# motor_driver.net
KiCad netlist of a schematic drawn in EAGLE
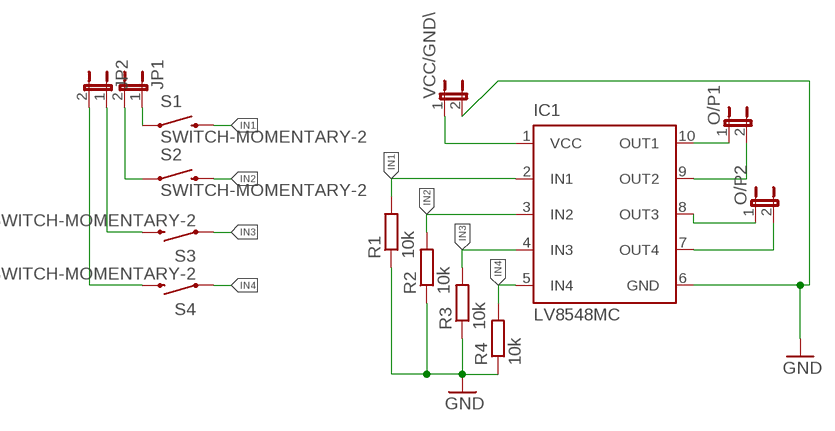
[diagram p0: schematic, sheet 1]

(export (version "E")
  (design (tool "Eeschema 10.0.6"))
  (components
    (comp (ref "IC1")
      (value "LV8548MC")
      (footprint "eagle-import:MFP10S")
      (libsource (lib "eagle-import") (part "LV8548MC"))
    )
    (comp (ref "JP1")
      (value "JP1E")
      (footprint "eagle-import:JP1")
      (libsource (lib "eagle-import") (part "JP1E"))
    )
    (comp (ref "JP2")
      (value "JP1E")
      (footprint "eagle-import:JP1")
      (libsource (lib "eagle-import") (part "JP1E"))
    )
    (comp (ref "O/P1")
      (value "JP1E")
      (footprint "eagle-import:JP1")
      (libsource (lib "eagle-import") (part "JP1E"))
    )
    (comp (ref "O/P2")
      (value "JP1E")
      (footprint "eagle-import:JP1")
      (libsource (lib "eagle-import") (part "JP1E"))
    )
    (comp (ref "R1")
      (value "10k")
      (footprint "eagle-import:R0603")
      (libsource (lib "eagle-import") (part "R-EU_R0603"))
    )
    (comp (ref "R2")
      (value "10k")
      (footprint "eagle-import:R0603")
      (libsource (lib "eagle-import") (part "R-EU_R0603"))
    )
    (comp (ref "R3")
      (value "10k")
      (footprint "eagle-import:R0603")
      (libsource (lib "eagle-import") (part "R-EU_R0603"))
    )
    (comp (ref "R4")
      (value "10k")
      (footprint "eagle-import:R0603")
      (libsource (lib "eagle-import") (part "R-EU_R0603"))
    )
    (comp (ref "S1")
      (value "SWITCH-MOMENTARY-2")
      (footprint "eagle-import:TACTILE_SWITCH_TALL")
      (libsource (lib "eagle-import") (part "SWITCH-MOMENTARY-2"))
    )
    (comp (ref "S2")
      (value "SWITCH-MOMENTARY-2")
      (footprint "eagle-import:TACTILE_SWITCH_TALL")
      (libsource (lib "eagle-import") (part "SWITCH-MOMENTARY-2"))
    )
    (comp (ref "S3")
      (value "SWITCH-MOMENTARY-2")
      (footprint "eagle-import:TACTILE_SWITCH_TALL")
      (libsource (lib "eagle-import") (part "SWITCH-MOMENTARY-2"))
    )
    (comp (ref "S4")
      (value "SWITCH-MOMENTARY-2")
      (footprint "eagle-import:TACTILE_SWITCH_TALL")
      (libsource (lib "eagle-import") (part "SWITCH-MOMENTARY-2"))
    )
    (comp (ref "VCC/GND\\")
      (value "JP1E")
      (footprint "eagle-import:JP1")
      (libsource (lib "eagle-import") (part "JP1E"))
    )
  )
  (nets
    (net (code "1") (name "GND") (class "Default")
      (node (ref "IC1") (pin "6") (pinfunction "GND_6") (pintype "bidirectional"))
      (node (ref "R1") (pin "1") (pinfunction "1_1") (pintype "passive"))
      (node (ref "R2") (pin "1") (pinfunction "1_1") (pintype "passive"))
      (node (ref "R3") (pin "1") (pinfunction "1_1") (pintype "passive"))
      (node (ref "R4") (pin "1") (pinfunction "1_1") (pintype "passive"))
      (node (ref "VCC/GND\\") (pin "2") (pinfunction "2_2") (pintype "passive"))
    )
    (net (code "2") (name "IN1") (class "Default")
      (node (ref "IC1") (pin "2") (pinfunction "IN1_2") (pintype "bidirectional"))
      (node (ref "R1") (pin "2") (pinfunction "2_2") (pintype "passive"))
      (node (ref "S1") (pin "B2") (pinfunction "2_B2") (pintype "passive"))
    )
    (net (code "3") (name "IN2") (class "Default")
      (node (ref "IC1") (pin "3") (pinfunction "IN2_3") (pintype "bidirectional"))
      (node (ref "R2") (pin "2") (pinfunction "2_2") (pintype "passive"))
      (node (ref "S2") (pin "B2") (pinfunction "2_B2") (pintype "passive"))
    )
    (net (code "4") (name "IN3") (class "Default")
      (node (ref "IC1") (pin "4") (pinfunction "IN3_4") (pintype "bidirectional"))
      (node (ref "R3") (pin "2") (pinfunction "2_2") (pintype "passive"))
      (node (ref "S3") (pin "A2") (pinfunction "1_A2") (pintype "passive"))
    )
    (net (code "5") (name "IN4") (class "Default")
      (node (ref "IC1") (pin "5") (pinfunction "IN4_5") (pintype "bidirectional"))
      (node (ref "R4") (pin "2") (pinfunction "2_2") (pintype "passive"))
      (node (ref "S4") (pin "A2") (pinfunction "1_A2") (pintype "passive"))
    )
    (net (code "6") (name "Net-(IC1-OUT1)") (class "Default")
      (node (ref "IC1") (pin "10") (pinfunction "OUT1_10") (pintype "bidirectional"))
      (node (ref "O/P1") (pin "1") (pinfunction "1_1") (pintype "passive"))
    )
    (net (code "7") (name "Net-(IC1-OUT2)") (class "Default")
      (node (ref "IC1") (pin "9") (pinfunction "OUT2_9") (pintype "bidirectional"))
      (node (ref "O/P1") (pin "2") (pinfunction "2_2") (pintype "passive"))
    )
    (net (code "8") (name "Net-(IC1-OUT3)") (class "Default")
      (node (ref "IC1") (pin "8") (pinfunction "OUT3_8") (pintype "bidirectional"))
      (node (ref "O/P2") (pin "1") (pinfunction "1_1") (pintype "passive"))
    )
    (net (code "9") (name "Net-(IC1-OUT4)") (class "Default")
      (node (ref "IC1") (pin "7") (pinfunction "OUT4_7") (pintype "bidirectional"))
      (node (ref "O/P2") (pin "2") (pinfunction "2_2") (pintype "passive"))
    )
    (net (code "10") (name "Net-(IC1-VCC)") (class "Default")
      (node (ref "IC1") (pin "1") (pinfunction "VCC_1") (pintype "bidirectional"))
      (node (ref "VCC/GND\\") (pin "1") (pinfunction "1_1") (pintype "passive"))
    )
    (net (code "11") (name "Net-(S1-1)") (class "Default")
      (node (ref "JP1") (pin "1") (pinfunction "1_1") (pintype "passive"))
      (node (ref "S1") (pin "A2") (pinfunction "1_A2") (pintype "passive"))
    )
    (net (code "12") (name "Net-(S2-1)") (class "Default")
      (node (ref "JP1") (pin "2") (pinfunction "2_2") (pintype "passive"))
      (node (ref "S2") (pin "A2") (pinfunction "1_A2") (pintype "passive"))
    )
    (net (code "13") (name "Net-(S3-2)") (class "Default")
      (node (ref "JP2") (pin "1") (pinfunction "1_1") (pintype "passive"))
      (node (ref "S3") (pin "B2") (pinfunction "2_B2") (pintype "passive"))
    )
    (net (code "14") (name "Net-(S4-2)") (class "Default")
      (node (ref "JP2") (pin "2") (pinfunction "2_2") (pintype "passive"))
      (node (ref "S4") (pin "B2") (pinfunction "2_B2") (pintype "passive"))
    )
  )
)
